# tweeq-STAMP_I2C_RTC_DS1338_v1.net
KiCad netlist of a schematic drawn in EAGLE
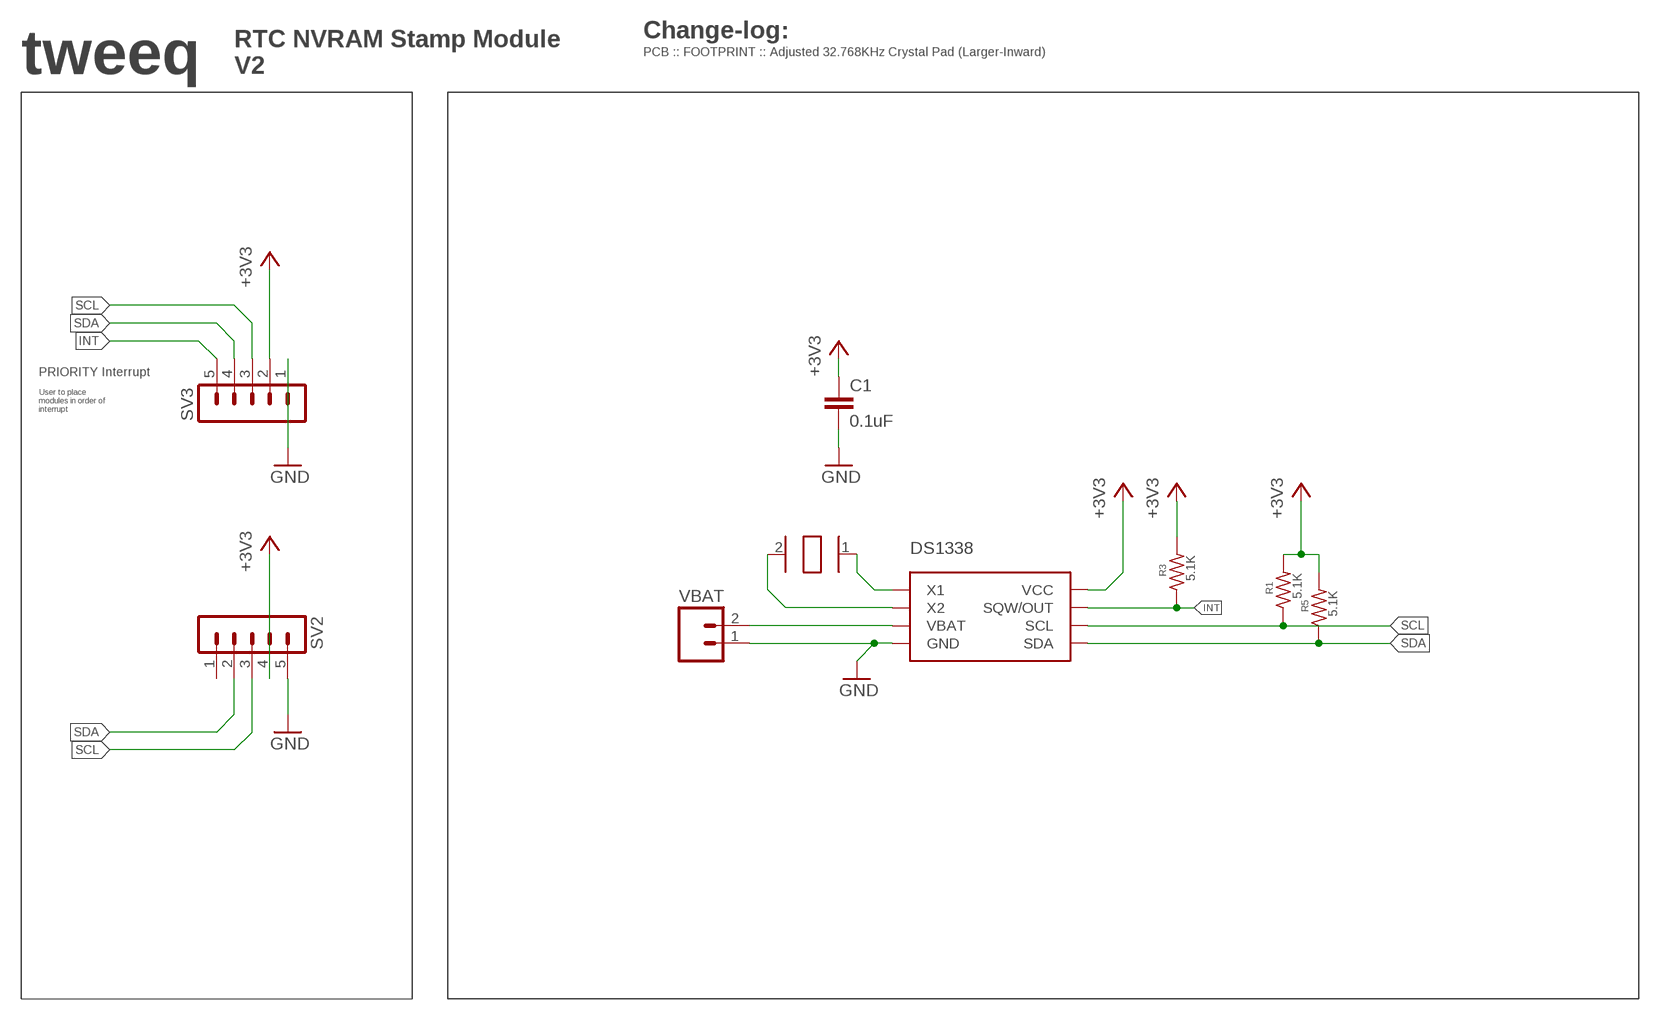
[diagram p0: schematic, sheet 1]

(export (version "E")
  (design (tool "Eeschema 10.0.6"))
  (components
    (comp (ref "C1")
      (value "0.1uF")
      (footprint "eagle-import:C0402K")
      (libsource (lib "eagle-import") (part "C-EUC0402K"))
    )
    (comp (ref "DS1338")
      (value "DS1338U")
      (footprint "eagle-import:MSOP8")
      (libsource (lib "eagle-import") (part "DS1338U"))
    )
    (comp (ref "R1")
      (value "5.1K")
      (footprint "eagle-import:R0402")
      (libsource (lib "eagle-import") (part "R-US_R0402"))
    )
    (comp (ref "R3")
      (value "5.1K")
      (footprint "eagle-import:R0402")
      (libsource (lib "eagle-import") (part "R-US_R0402"))
    )
    (comp (ref "R5")
      (value "5.1K")
      (footprint "eagle-import:R0402")
      (libsource (lib "eagle-import") (part "R-US_R0402"))
    )
    (comp (ref "SV2")
      (value "M05-1STAMP")
      (footprint "eagle-import:1X05-1.5MM-STAMP")
      (libsource (lib "eagle-import") (part "M05-1STAMP"))
    )
    (comp (ref "SV3")
      (value "M05-1STAMP")
      (footprint "eagle-import:1X05-1.5MM-STAMP")
      (libsource (lib "eagle-import") (part "M05-1STAMP"))
    )
    (comp (ref "U$2")
      (value "32.765KHZ_CRYSTALABS07")
      (footprint "eagle-import:ABS07")
      (libsource (lib "eagle-import") (part "32.765KHZ_CRYSTALABS07"))
    )
    (comp (ref "VBAT")
      (value "M021X02_SMD_SQUARE")
      (footprint "eagle-import:1X02_SMD")
      (libsource (lib "eagle-import") (part "M021X02_SMD_SQUARE"))
    )
  )
  (nets
    (net (code "1") (name "+3V3") (class "Default")
      (node (ref "C1") (pin "1") (pinfunction "1_1") (pintype "passive"))
      (node (ref "DS1338") (pin "8") (pinfunction "VCC_8") (pintype "bidirectional"))
      (node (ref "R1") (pin "2") (pinfunction "2_2") (pintype "passive"))
      (node (ref "R3") (pin "2") (pinfunction "2_2") (pintype "passive"))
      (node (ref "R5") (pin "2") (pinfunction "2_2") (pintype "passive"))
      (node (ref "SV2") (pin "4") (pinfunction "4_4") (pintype "passive"))
      (node (ref "SV3") (pin "2") (pinfunction "2_2") (pintype "passive"))
    )
    (net (code "2") (name "GND") (class "Default")
      (node (ref "C1") (pin "2") (pinfunction "2_2") (pintype "passive"))
      (node (ref "DS1338") (pin "4") (pinfunction "GND_4") (pintype "bidirectional"))
      (node (ref "SV2") (pin "5") (pinfunction "5_5") (pintype "passive"))
      (node (ref "SV3") (pin "1") (pinfunction "1_1") (pintype "passive"))
      (node (ref "VBAT") (pin "1") (pinfunction "1_1") (pintype "passive"))
    )
    (net (code "3") (name "INT") (class "Default")
      (node (ref "DS1338") (pin "7") (pinfunction "SQW/OUT_7") (pintype "bidirectional"))
      (node (ref "R3") (pin "1") (pinfunction "1_1") (pintype "passive"))
      (node (ref "SV3") (pin "5") (pinfunction "5_5") (pintype "passive"))
    )
    (net (code "4") (name "Net-(DS1338-VBAT)") (class "Default")
      (node (ref "DS1338") (pin "3") (pinfunction "VBAT_3") (pintype "bidirectional"))
      (node (ref "VBAT") (pin "2") (pinfunction "2_2") (pintype "passive"))
    )
    (net (code "5") (name "Net-(DS1338-X1)") (class "Default")
      (node (ref "DS1338") (pin "1") (pinfunction "X1_1") (pintype "bidirectional"))
      (node (ref "U$2") (pin "1") (pinfunction "P$1_1") (pintype "bidirectional"))
    )
    (net (code "6") (name "Net-(DS1338-X2)") (class "Default")
      (node (ref "DS1338") (pin "2") (pinfunction "X2_2") (pintype "bidirectional"))
      (node (ref "U$2") (pin "2") (pinfunction "P$2_2") (pintype "bidirectional"))
    )
    (net (code "7") (name "SCL") (class "Default")
      (node (ref "DS1338") (pin "6") (pinfunction "SCL_6") (pintype "bidirectional"))
      (node (ref "R1") (pin "1") (pinfunction "1_1") (pintype "passive"))
      (node (ref "SV2") (pin "3") (pinfunction "3_3") (pintype "passive"))
      (node (ref "SV3") (pin "3") (pinfunction "3_3") (pintype "passive"))
    )
    (net (code "8") (name "SDA") (class "Default")
      (node (ref "DS1338") (pin "5") (pinfunction "SDA_5") (pintype "bidirectional"))
      (node (ref "R5") (pin "1") (pinfunction "1_1") (pintype "passive"))
      (node (ref "SV2") (pin "2") (pinfunction "2_2") (pintype "passive"))
      (node (ref "SV3") (pin "4") (pinfunction "4_4") (pintype "passive"))
    )
    (net (code "9") (name "unconnected-(SV2-Pad1)") (class "Default")
      (node (ref "SV2") (pin "1") (pinfunction "1_1") (pintype "passive"))
    )
  )
)
